# QEDTiny.net
KiCad netlist of a schematic drawn in EAGLE
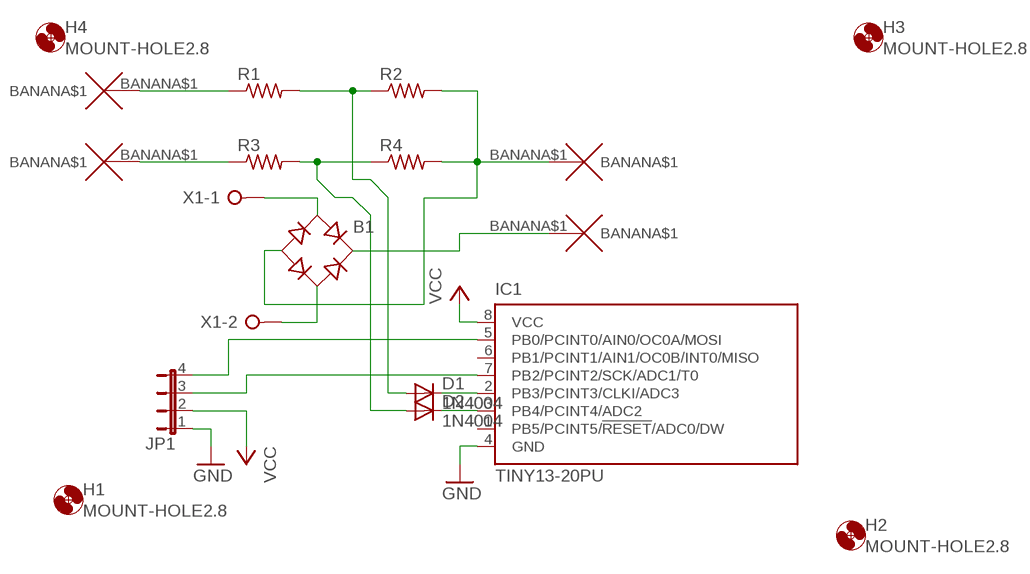
[diagram p0: schematic, sheet 1]

(export (version "E")
  (design (tool "Eeschema 10.0.6"))
  (components
    (comp (ref "B1")
      (value "RB1A")
      (footprint "eagle-import:RB1A")
      (libsource (lib "eagle-import") (part "RB1A"))
    )
    (comp (ref "D1")
      (value "1N4004")
      (footprint "eagle-import:DO41-10")
      (libsource (lib "eagle-import") (part "1N4004"))
    )
    (comp (ref "D2")
      (value "1N4004")
      (footprint "eagle-import:DO41-10")
      (libsource (lib "eagle-import") (part "1N4004"))
    )
    (comp (ref "H1")
      (value "MOUNT-HOLE2.8")
      (footprint "eagle-import:2,8")
      (libsource (lib "eagle-import") (part "MOUNT-HOLE2.8"))
    )
    (comp (ref "H2")
      (value "MOUNT-HOLE2.8")
      (footprint "eagle-import:2,8")
      (libsource (lib "eagle-import") (part "MOUNT-HOLE2.8"))
    )
    (comp (ref "H3")
      (value "MOUNT-HOLE2.8")
      (footprint "eagle-import:2,8")
      (libsource (lib "eagle-import") (part "MOUNT-HOLE2.8"))
    )
    (comp (ref "H4")
      (value "MOUNT-HOLE2.8")
      (footprint "eagle-import:2,8")
      (libsource (lib "eagle-import") (part "MOUNT-HOLE2.8"))
    )
    (comp (ref "IC1")
      (value "TINY13-20PU")
      (footprint "eagle-import:DIL08")
      (fields (field (name "MPN") "ATTINY13-20PU"))
      (libsource (lib "eagle-import") (part "TINY13PU-20"))
    )
    (comp (ref "JP1")
      (value "JP4E")
      (footprint "eagle-import:JP4")
      (libsource (lib "eagle-import") (part "JP4E"))
    )
    (comp (ref "R1")
      (value "R-US_0207/7")
      (footprint "eagle-import:0207_7")
      (libsource (lib "eagle-import") (part "R-US_0207/7"))
    )
    (comp (ref "R2")
      (value "R-US_0207/7")
      (footprint "eagle-import:0207_7")
      (libsource (lib "eagle-import") (part "R-US_0207/7"))
    )
    (comp (ref "R3")
      (value "R-US_0207/7")
      (footprint "eagle-import:0207_7")
      (libsource (lib "eagle-import") (part "R-US_0207/7"))
    )
    (comp (ref "R4")
      (value "R-US_0207/7")
      (footprint "eagle-import:0207_7")
      (libsource (lib "eagle-import") (part "R-US_0207/7"))
    )
    (comp (ref "U$1")
      (value "BANANA")
      (footprint "eagle-import:BANANA")
      (libsource (lib "eagle-import") (part "BANANA"))
    )
    (comp (ref "U$2")
      (value "BANANA")
      (footprint "eagle-import:BANANA")
      (libsource (lib "eagle-import") (part "BANANA"))
    )
    (comp (ref "U$3")
      (value "BANANA")
      (footprint "eagle-import:BANANA")
      (libsource (lib "eagle-import") (part "BANANA"))
    )
    (comp (ref "U$4")
      (value "BANANA")
      (footprint "eagle-import:BANANA")
      (libsource (lib "eagle-import") (part "BANANA"))
    )
    (comp (ref "X1")
      (value "W237-02P")
      (footprint "eagle-import:W237-132")
      (libsource (lib "eagle-import") (part "W237-02P"))
    )
  )
  (nets
    (net (code "1") (name "GND") (class "Default")
      (node (ref "IC1") (pin "4") (pinfunction "GND_4") (pintype "power_in"))
      (node (ref "JP1") (pin "1") (pinfunction "1_1") (pintype "passive"))
    )
    (net (code "2") (name "Net-(B1-Pad+)") (class "Default")
      (node (ref "B1") (pin "+") (pinfunction "+_+") (pintype "passive"))
      (node (ref "U$1") (pin "BANANA$1") (pinfunction "BANANA$1_BANANA$1") (pintype "bidirectional"))
    )
    (net (code "3") (name "Net-(B1-Pad-)") (class "Default")
      (node (ref "B1") (pin "-") (pinfunction "-_-") (pintype "passive"))
      (node (ref "R2") (pin "2") (pinfunction "2_2") (pintype "passive"))
      (node (ref "R4") (pin "2") (pinfunction "2_2") (pintype "passive"))
      (node (ref "U$2") (pin "BANANA$1") (pinfunction "BANANA$1_BANANA$1") (pintype "bidirectional"))
    )
    (net (code "4") (name "Net-(D1-PadA)") (class "Default")
      (node (ref "D1") (pin "A") (pinfunction "A_A") (pintype "passive"))
      (node (ref "R1") (pin "2") (pinfunction "2_2") (pintype "passive"))
      (node (ref "R2") (pin "1") (pinfunction "1_1") (pintype "passive"))
    )
    (net (code "5") (name "Net-(D2-PadA)") (class "Default")
      (node (ref "D2") (pin "A") (pinfunction "A_A") (pintype "passive"))
      (node (ref "R3") (pin "2") (pinfunction "2_2") (pintype "passive"))
      (node (ref "R4") (pin "1") (pinfunction "1_1") (pintype "passive"))
    )
    (net (code "6") (name "Net-(IC1-PB0{slash}PCINT0{slash}AIN0{slash}OC0A{slash}MOSI)") (class "Default")
      (node (ref "IC1") (pin "5") (pinfunction "PB0/PCINT0/AIN0/OC0A/MOSI_5") (pintype "bidirectional"))
      (node (ref "JP1") (pin "4") (pinfunction "4_4") (pintype "passive"))
    )
    (net (code "7") (name "Net-(IC1-PB2{slash}PCINT2{slash}SCK{slash}ADC1{slash}T0)") (class "Default")
      (node (ref "IC1") (pin "7") (pinfunction "PB2/PCINT2/SCK/ADC1/T0_7") (pintype "bidirectional"))
      (node (ref "JP1") (pin "3") (pinfunction "3_3") (pintype "passive"))
    )
    (net (code "8") (name "Net-(IC1-PB3{slash}PCINT3{slash}CLKI{slash}ADC3)") (class "Default")
      (node (ref "D1") (pin "C") (pinfunction "C_C") (pintype "passive"))
      (node (ref "IC1") (pin "2") (pinfunction "PB3/PCINT3/CLKI/ADC3_2") (pintype "bidirectional"))
    )
    (net (code "9") (name "Net-(IC1-PB4{slash}PCINT4{slash}ADC2)") (class "Default")
      (node (ref "D2") (pin "C") (pinfunction "C_C") (pintype "passive"))
      (node (ref "IC1") (pin "3") (pinfunction "PB4/PCINT4/ADC2_3") (pintype "bidirectional"))
    )
    (net (code "10") (name "Net-(R1-Pad1)") (class "Default")
      (node (ref "R1") (pin "1") (pinfunction "1_1") (pintype "passive"))
      (node (ref "U$3") (pin "BANANA$1") (pinfunction "BANANA$1_BANANA$1") (pintype "bidirectional"))
    )
    (net (code "11") (name "Net-(R3-Pad1)") (class "Default")
      (node (ref "R3") (pin "1") (pinfunction "1_1") (pintype "passive"))
      (node (ref "U$4") (pin "BANANA$1") (pinfunction "BANANA$1_BANANA$1") (pintype "bidirectional"))
    )
    (net (code "12") (name "Net-(X1A-KL)") (class "Default")
      (node (ref "B1") (pin "AC1") (pinfunction "AC1_AC1") (pintype "passive"))
      (node (ref "X1") (pin "1") (pinfunction "KL_1") (pintype "passive"))
    )
    (net (code "13") (name "Net-(X1B-KL)") (class "Default")
      (node (ref "B1") (pin "AC2") (pinfunction "AC2_AC2") (pintype "passive"))
      (node (ref "X1") (pin "2") (pinfunction "KL_2") (pintype "passive"))
    )
    (net (code "14") (name "VCC") (class "Default")
      (node (ref "IC1") (pin "8") (pinfunction "VCC_8") (pintype "power_in"))
      (node (ref "JP1") (pin "2") (pinfunction "2_2") (pintype "passive"))
    )
    (net (code "15") (name "unconnected-(IC1-PB1{slash}PCINT1{slash}AIN1{slash}OC0B{slash}INT0{slash}MISO-Pad6)") (class "Default")
      (node (ref "IC1") (pin "6") (pinfunction "PB1/PCINT1/AIN1/OC0B/INT0/MISO_6") (pintype "bidirectional"))
    )
    (net (code "16") (name "unconnected-(IC1-PB5{slash}PCINT5{slash}~{RESET}{slash}ADC0{slash}DW-Pad1)") (class "Default")
      (node (ref "IC1") (pin "1") (pinfunction "PB5/PCINT5/~{RESET}/ADC0/DW_1") (pintype "bidirectional"))
    )
  )
)
